# GYRO-ACCELEROMETER.net
KiCad netlist of a schematic drawn in Altium Designer
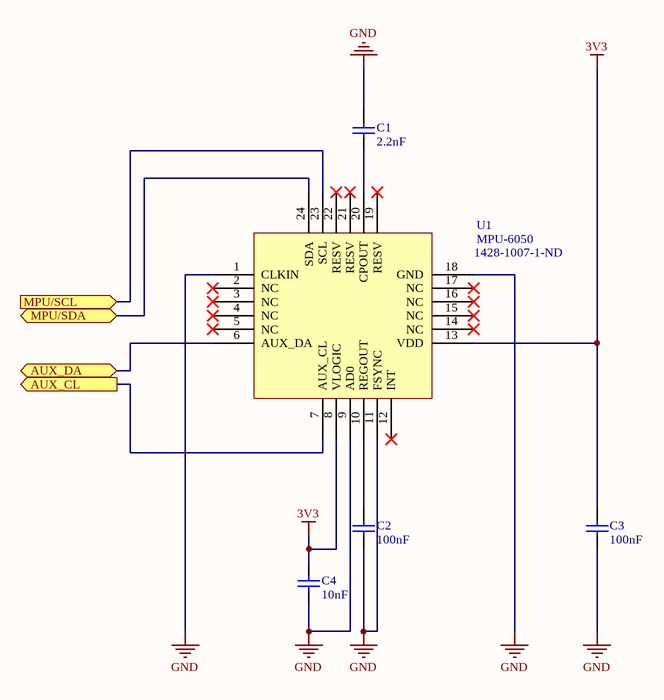
[diagram p0: GYRO-ACCELEROMETER.SchDoc]

(export (version "E")
  (design (tool "Eeschema 10.0.6"))
  (components
    (comp (ref "C1")
      (value "2.2nF")
      (footprint "C0603(1608)")
      (description "Capacitor")
      (libsource (lib "Miscellaneous Devices") (part "Cap"))
    )
    (comp (ref "C2")
      (value "100nF")
      (footprint "C0603(1608)")
      (description "Capacitor")
      (libsource (lib "Miscellaneous Devices") (part "Cap"))
    )
    (comp (ref "C3")
      (value "100nF")
      (footprint "C0603(1608)")
      (description "Capacitor")
      (libsource (lib "Miscellaneous Devices") (part "Cap"))
    )
    (comp (ref "C4")
      (value "10nF")
      (footprint "C0603(1608)")
      (description "Capacitor")
      (libsource (lib "Miscellaneous Devices") (part "Cap"))
    )
    (comp (ref "U1")
      (value "MPU-6050")
      (footprint "LGA 24")
      (description "INVENSENSE - MPU-6050 - GYRO / ACCEL, 6-AXIS, I2C, QFN-24")
      (fields
        (field (name "SUPPLIER PART NUMBER 1") "1428-1007-1-ND")
        (field (name "MANUFACTURER") "TDK InvenSense")
      )
      (libsource (lib "ATS_v1.1") (part "MPU-9150"))
    )
  )
  (nets
    (net (code "1") (name "/AUX_CL") (class "Default")
      (node (ref "U1") (pin "7") (pinfunction "AUX_CL_7") (pintype "passive"))
    )
    (net (code "2") (name "/AUX_DA") (class "Default")
      (node (ref "U1") (pin "6") (pinfunction "AUX_DA_6") (pintype "passive"))
    )
    (net (code "3") (name "/MPU{slash}SCL") (class "Default")
      (node (ref "U1") (pin "23") (pinfunction "SCL_23") (pintype "passive"))
    )
    (net (code "4") (name "/MPU{slash}SDA") (class "Default")
      (node (ref "U1") (pin "24") (pinfunction "SDA_24") (pintype "passive"))
    )
    (net (code "5") (name "3V3") (class "Default")
      (node (ref "C3") (pin "2") (pinfunction "2_2") (pintype "passive"))
      (node (ref "C4") (pin "2") (pinfunction "2_2") (pintype "passive"))
      (node (ref "U1") (pin "13") (pinfunction "VDD_13") (pintype "passive"))
      (node (ref "U1") (pin "8") (pinfunction "VLOGIC_8") (pintype "passive"))
    )
    (net (code "6") (name "GND") (class "Default")
      (node (ref "C1") (pin "1") (pinfunction "1_1") (pintype "passive"))
      (node (ref "C2") (pin "1") (pinfunction "1_1") (pintype "passive"))
      (node (ref "C3") (pin "1") (pinfunction "1_1") (pintype "passive"))
      (node (ref "C4") (pin "1") (pinfunction "1_1") (pintype "passive"))
      (node (ref "U1") (pin "1") (pinfunction "CLKIN_1") (pintype "passive"))
      (node (ref "U1") (pin "11") (pinfunction "FSYNC_11") (pintype "passive"))
      (node (ref "U1") (pin "18") (pinfunction "GND_18") (pintype "passive"))
      (node (ref "U1") (pin "9") (pinfunction "AD0_9") (pintype "passive"))
    )
    (net (code "7") (name "Net-(U1-CPOUT)") (class "Default")
      (node (ref "C1") (pin "2") (pinfunction "2_2") (pintype "passive"))
      (node (ref "U1") (pin "20") (pinfunction "CPOUT_20") (pintype "passive"))
    )
    (net (code "8") (name "Net-(U1-REGOUT)") (class "Default")
      (node (ref "C2") (pin "2") (pinfunction "2_2") (pintype "passive"))
      (node (ref "U1") (pin "10") (pinfunction "REGOUT_10") (pintype "passive"))
    )
    (net (code "9") (name "unconnected-(U1-INT-Pad12)") (class "Default")
      (node (ref "U1") (pin "12") (pinfunction "INT_12") (pintype "passive+no_connect"))
    )
    (net (code "10") (name "unconnected-(U1-NC-Pad2)") (class "Default")
      (node (ref "U1") (pin "2") (pinfunction "NC_2") (pintype "passive+no_connect"))
    )
    (net (code "11") (name "unconnected-(U1-NC-Pad3)") (class "Default")
      (node (ref "U1") (pin "3") (pinfunction "NC_3") (pintype "passive+no_connect"))
    )
    (net (code "12") (name "unconnected-(U1-NC-Pad4)") (class "Default")
      (node (ref "U1") (pin "4") (pinfunction "NC_4") (pintype "passive+no_connect"))
    )
    (net (code "13") (name "unconnected-(U1-NC-Pad5)") (class "Default")
      (node (ref "U1") (pin "5") (pinfunction "NC_5") (pintype "passive+no_connect"))
    )
    (net (code "14") (name "unconnected-(U1-NC-Pad14)") (class "Default")
      (node (ref "U1") (pin "14") (pinfunction "NC_14") (pintype "passive+no_connect"))
    )
    (net (code "15") (name "unconnected-(U1-NC-Pad15)") (class "Default")
      (node (ref "U1") (pin "15") (pinfunction "NC_15") (pintype "passive+no_connect"))
    )
    (net (code "16") (name "unconnected-(U1-NC-Pad16)") (class "Default")
      (node (ref "U1") (pin "16") (pinfunction "NC_16") (pintype "passive+no_connect"))
    )
    (net (code "17") (name "unconnected-(U1-NC-Pad17)") (class "Default")
      (node (ref "U1") (pin "17") (pinfunction "NC_17") (pintype "passive+no_connect"))
    )
    (net (code "18") (name "unconnected-(U1-RESV-Pad19)") (class "Default")
      (node (ref "U1") (pin "19") (pinfunction "RESV_19") (pintype "passive+no_connect"))
    )
    (net (code "19") (name "unconnected-(U1-RESV-Pad21)") (class "Default")
      (node (ref "U1") (pin "21") (pinfunction "RESV_21") (pintype "passive+no_connect"))
    )
    (net (code "20") (name "unconnected-(U1-RESV-Pad22)") (class "Default")
      (node (ref "U1") (pin "22") (pinfunction "RESV_22") (pintype "passive+no_connect"))
    )
  )
)
